# 8_Arm.net
KiCad netlist of a schematic drawn in Altium Designer
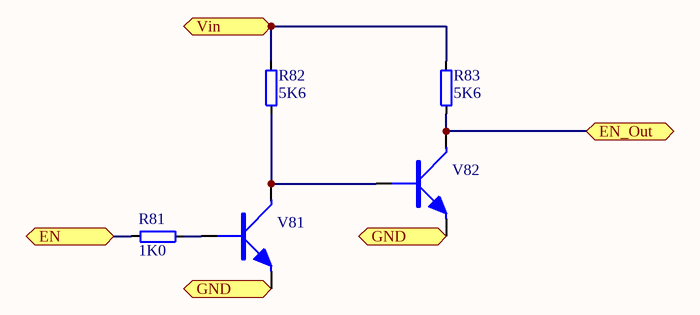
[diagram p0: 8_Arm.SchDoc]

(export (version "E")
  (design (tool "Eeschema 10.0.6"))
  (components
    (comp (ref "R81")
      (value "1K0")
      (footprint "0805")
      (description "Resistor")
      (fields
        (field (name "MANUFACTURER") "Phycomp")
        (field (name "PARTNUMBER") "RC0805FR-071KL")
        (field (name "CHECKEDBY") "ART")
      )
      (libsource (lib "SVN_BOMGEN_Database_2014") (part "RES"))
    )
    (comp (ref "R82")
      (value "5K6")
      (footprint "0805")
      (description "Resistor")
      (fields
        (field (name "MANUFACTURER") "Phycomp")
        (field (name "PARTNUMBER") "RC0805FR-075K6L")
        (field (name "CHECKEDBY") "ART")
      )
      (libsource (lib "SVN_BOMGEN_Database_2014") (part "RES"))
    )
    (comp (ref "R83")
      (value "5K6")
      (footprint "0805")
      (description "Resistor")
      (fields
        (field (name "MANUFACTURER") "Phycomp")
        (field (name "PARTNUMBER") "RC0805FR-075K6L")
        (field (name "CHECKEDBY") "ART")
      )
      (libsource (lib "SVN_BOMGEN_Database_2014") (part "RES"))
    )
    (comp (ref "V81")
      (value "BC846B")
      (footprint "SOT23")
      (description "NPN Transistor SOT23")
      (fields (field (name "MANUFACTURER") "NXP") (field (name "CHECKEDBY") "LZZ"))
      (libsource (lib "SVN_BOMGEN_Database_2014") (part "NPN-SOT23"))
    )
    (comp (ref "V82")
      (value "BC846B")
      (footprint "SOT23")
      (description "NPN Transistor SOT23")
      (fields (field (name "MANUFACTURER") "NXP") (field (name "CHECKEDBY") "LZZ"))
      (libsource (lib "SVN_BOMGEN_Database_2014") (part "NPN-SOT23"))
    )
  )
  (nets
    (net (code "1") (name "/EN") (class "Default")
      (node (ref "R81") (pin "1") (pinfunction "1_1") (pintype "passive"))
    )
    (net (code "2") (name "/EN_Out") (class "Default")
      (node (ref "R83") (pin "1") (pinfunction "1_1") (pintype "passive"))
      (node (ref "V82") (pin "x") (pinfunction "Collector_x") (pintype "passive"))
    )
    (net (code "3") (name "/GND") (class "Default")
      (node (ref "V81") (pin "y") (pinfunction "Emitter_y") (pintype "passive"))
      (node (ref "V82") (pin "y") (pinfunction "Emitter_y") (pintype "passive"))
    )
    (net (code "4") (name "/Vin") (class "Default")
      (node (ref "R82") (pin "2") (pinfunction "2_2") (pintype "passive"))
      (node (ref "R83") (pin "2") (pinfunction "2_2") (pintype "passive"))
    )
    (net (code "5") (name "Net-(V81-Base)") (class "Default")
      (node (ref "R81") (pin "2") (pinfunction "2_2") (pintype "passive"))
      (node (ref "V81") (pin "z") (pinfunction "Base_z") (pintype "passive"))
    )
    (net (code "6") (name "Net-(V81-Collector)") (class "Default")
      (node (ref "R82") (pin "1") (pinfunction "1_1") (pintype "passive"))
      (node (ref "V81") (pin "x") (pinfunction "Collector_x") (pintype "passive"))
      (node (ref "V82") (pin "z") (pinfunction "Base_z") (pintype "passive"))
    )
  )
)
